# SparkySpecialKExpansion.net
KiCad netlist of a schematic drawn in EAGLE
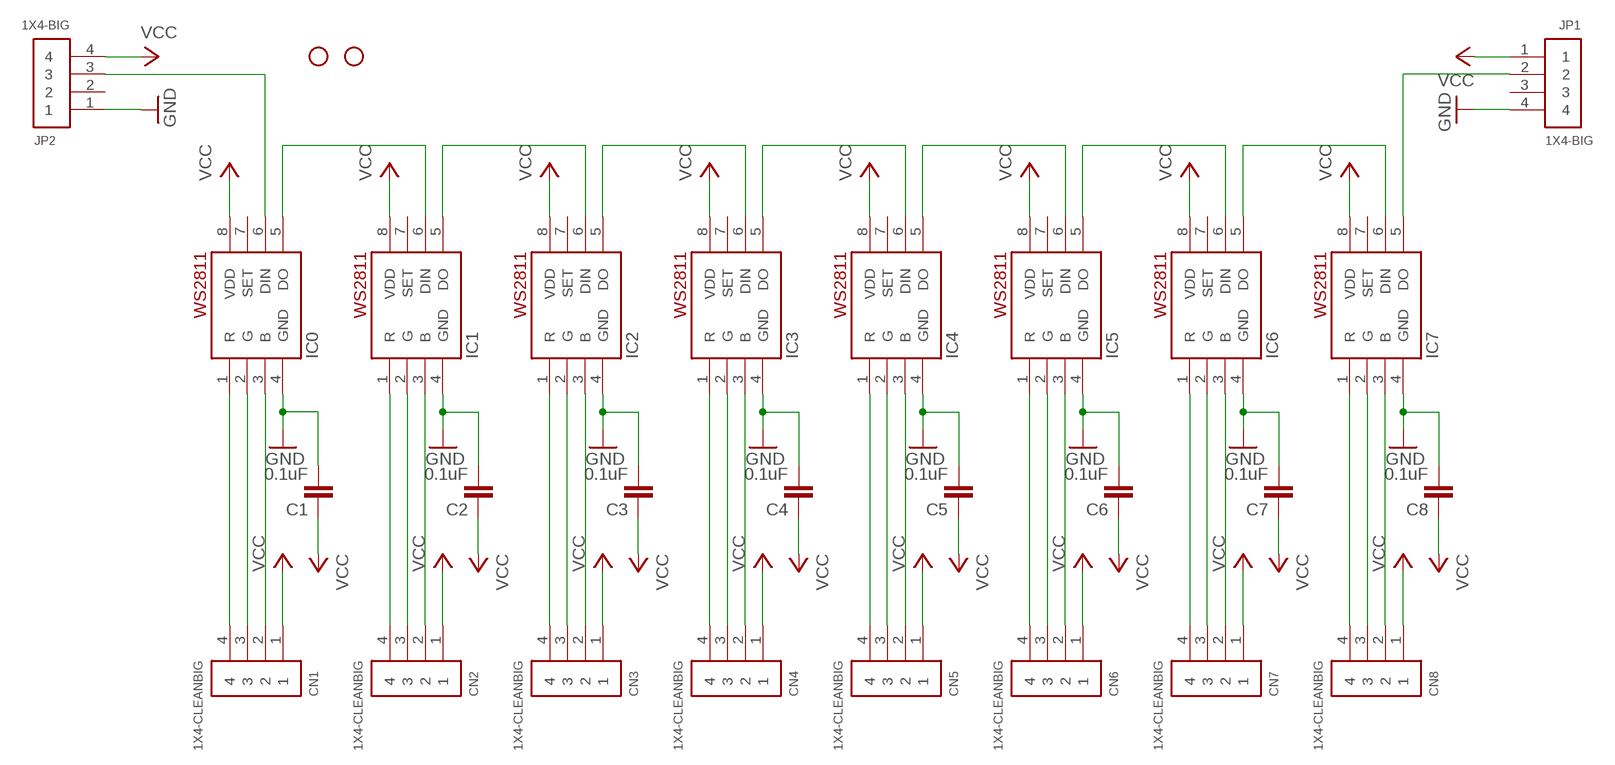
[diagram p0: schematic, sheet 1]

(export (version "E")
  (design (tool "Eeschema 10.0.6"))
  (components
    (comp (ref "C1")
      (value "0.1uF")
      (footprint "eagle-import:0805")
      (libsource (lib "eagle-import") (part "CAP0805"))
    )
    (comp (ref "C2")
      (value "0.1uF")
      (footprint "eagle-import:0805")
      (libsource (lib "eagle-import") (part "CAP0805"))
    )
    (comp (ref "C3")
      (value "0.1uF")
      (footprint "eagle-import:0805")
      (libsource (lib "eagle-import") (part "CAP0805"))
    )
    (comp (ref "C4")
      (value "0.1uF")
      (footprint "eagle-import:0805")
      (libsource (lib "eagle-import") (part "CAP0805"))
    )
    (comp (ref "C5")
      (value "0.1uF")
      (footprint "eagle-import:0805")
      (libsource (lib "eagle-import") (part "CAP0805"))
    )
    (comp (ref "C6")
      (value "0.1uF")
      (footprint "eagle-import:0805")
      (libsource (lib "eagle-import") (part "CAP0805"))
    )
    (comp (ref "C7")
      (value "0.1uF")
      (footprint "eagle-import:0805")
      (libsource (lib "eagle-import") (part "CAP0805"))
    )
    (comp (ref "C8")
      (value "0.1uF")
      (footprint "eagle-import:0805")
      (libsource (lib "eagle-import") (part "CAP0805"))
    )
    (comp (ref "CN1")
      (value "1X4-CLEANBIG")
      (footprint "eagle-import:1X04-CLEANBIG")
      (libsource (lib "eagle-import") (part "1X4-CLEANBIG"))
    )
    (comp (ref "CN2")
      (value "1X4-CLEANBIG")
      (footprint "eagle-import:1X04-CLEANBIG")
      (libsource (lib "eagle-import") (part "1X4-CLEANBIG"))
    )
    (comp (ref "CN3")
      (value "1X4-CLEANBIG")
      (footprint "eagle-import:1X04-CLEANBIG")
      (libsource (lib "eagle-import") (part "1X4-CLEANBIG"))
    )
    (comp (ref "CN4")
      (value "1X4-CLEANBIG")
      (footprint "eagle-import:1X04-CLEANBIG")
      (libsource (lib "eagle-import") (part "1X4-CLEANBIG"))
    )
    (comp (ref "CN5")
      (value "1X4-CLEANBIG")
      (footprint "eagle-import:1X04-CLEANBIG")
      (libsource (lib "eagle-import") (part "1X4-CLEANBIG"))
    )
    (comp (ref "CN6")
      (value "1X4-CLEANBIG")
      (footprint "eagle-import:1X04-CLEANBIG")
      (libsource (lib "eagle-import") (part "1X4-CLEANBIG"))
    )
    (comp (ref "CN7")
      (value "1X4-CLEANBIG")
      (footprint "eagle-import:1X04-CLEANBIG")
      (libsource (lib "eagle-import") (part "1X4-CLEANBIG"))
    )
    (comp (ref "CN8")
      (value "1X4-CLEANBIG")
      (footprint "eagle-import:1X04-CLEANBIG")
      (libsource (lib "eagle-import") (part "1X4-CLEANBIG"))
    )
    (comp (ref "IC0")
      (value "WS2811-SOP8")
      (footprint "eagle-import:SO08-SKINNYPADS")
      (libsource (lib "eagle-import") (part "WS2811-SOP8"))
    )
    (comp (ref "IC1")
      (value "WS2811-SOP8")
      (footprint "eagle-import:SO08-SKINNYPADS")
      (libsource (lib "eagle-import") (part "WS2811-SOP8"))
    )
    (comp (ref "IC2")
      (value "WS2811-SOP8")
      (footprint "eagle-import:SO08-SKINNYPADS")
      (libsource (lib "eagle-import") (part "WS2811-SOP8"))
    )
    (comp (ref "IC3")
      (value "WS2811-SOP8")
      (footprint "eagle-import:SO08-SKINNYPADS")
      (libsource (lib "eagle-import") (part "WS2811-SOP8"))
    )
    (comp (ref "IC4")
      (value "WS2811-SOP8")
      (footprint "eagle-import:SO08-SKINNYPADS")
      (libsource (lib "eagle-import") (part "WS2811-SOP8"))
    )
    (comp (ref "IC5")
      (value "WS2811-SOP8")
      (footprint "eagle-import:SO08-SKINNYPADS")
      (libsource (lib "eagle-import") (part "WS2811-SOP8"))
    )
    (comp (ref "IC6")
      (value "WS2811-SOP8")
      (footprint "eagle-import:SO08-SKINNYPADS")
      (libsource (lib "eagle-import") (part "WS2811-SOP8"))
    )
    (comp (ref "IC7")
      (value "WS2811-SOP8")
      (footprint "eagle-import:SO08-SKINNYPADS")
      (libsource (lib "eagle-import") (part "WS2811-SOP8"))
    )
    (comp (ref "JP1")
      (value "1X4-BIG")
      (footprint "eagle-import:1X04-BIG")
      (libsource (lib "eagle-import") (part "1X4-BIG"))
    )
    (comp (ref "JP2")
      (value "1X4-BIG")
      (footprint "eagle-import:1X04-BIG")
      (libsource (lib "eagle-import") (part "1X4-BIG"))
    )
    (comp (ref "JP3")
      (value "STAND-OFF")
      (footprint "eagle-import:STAND-OFF")
      (libsource (lib "eagle-import") (part "STAND-OFF"))
    )
    (comp (ref "JP4")
      (value "STAND-OFF")
      (footprint "eagle-import:STAND-OFF")
      (libsource (lib "eagle-import") (part "STAND-OFF"))
    )
  )
  (nets
    (net (code "1") (name "GND") (class "Default")
      (node (ref "C1") (pin "2") (pinfunction "2_2") (pintype "passive"))
      (node (ref "C2") (pin "2") (pinfunction "2_2") (pintype "passive"))
      (node (ref "C3") (pin "2") (pinfunction "2_2") (pintype "passive"))
      (node (ref "C4") (pin "2") (pinfunction "2_2") (pintype "passive"))
      (node (ref "C5") (pin "2") (pinfunction "2_2") (pintype "passive"))
      (node (ref "C6") (pin "2") (pinfunction "2_2") (pintype "passive"))
      (node (ref "C7") (pin "2") (pinfunction "2_2") (pintype "passive"))
      (node (ref "C8") (pin "2") (pinfunction "2_2") (pintype "passive"))
      (node (ref "IC0") (pin "4") (pinfunction "GND_4") (pintype "power_in"))
      (node (ref "IC1") (pin "4") (pinfunction "GND_4") (pintype "power_in"))
      (node (ref "IC2") (pin "4") (pinfunction "GND_4") (pintype "power_in"))
      (node (ref "IC3") (pin "4") (pinfunction "GND_4") (pintype "power_in"))
      (node (ref "IC4") (pin "4") (pinfunction "GND_4") (pintype "power_in"))
      (node (ref "IC5") (pin "4") (pinfunction "GND_4") (pintype "power_in"))
      (node (ref "IC6") (pin "4") (pinfunction "GND_4") (pintype "power_in"))
      (node (ref "IC7") (pin "4") (pinfunction "GND_4") (pintype "power_in"))
      (node (ref "JP1") (pin "4") (pinfunction "4_4") (pintype "bidirectional"))
      (node (ref "JP2") (pin "1") (pinfunction "1_1") (pintype "bidirectional"))
    )
    (net (code "2") (name "Net-(IC0-B)") (class "Default")
      (node (ref "CN1") (pin "2") (pinfunction "2_2") (pintype "bidirectional"))
      (node (ref "IC0") (pin "3") (pinfunction "B_3") (pintype "open_collector"))
    )
    (net (code "3") (name "Net-(IC0-DIN)") (class "Default")
      (node (ref "IC0") (pin "6") (pinfunction "DIN_6") (pintype "input"))
      (node (ref "JP2") (pin "3") (pinfunction "3_3") (pintype "bidirectional"))
    )
    (net (code "4") (name "Net-(IC0-DO)") (class "Default")
      (node (ref "IC0") (pin "5") (pinfunction "DO_5") (pintype "output"))
      (node (ref "IC1") (pin "6") (pinfunction "DIN_6") (pintype "input"))
    )
    (net (code "5") (name "Net-(IC0-G)") (class "Default")
      (node (ref "CN1") (pin "3") (pinfunction "3_3") (pintype "bidirectional"))
      (node (ref "IC0") (pin "2") (pinfunction "G_2") (pintype "open_collector"))
    )
    (net (code "6") (name "Net-(IC0-R)") (class "Default")
      (node (ref "CN1") (pin "4") (pinfunction "4_4") (pintype "bidirectional"))
      (node (ref "IC0") (pin "1") (pinfunction "R_1") (pintype "open_collector"))
    )
    (net (code "7") (name "Net-(IC1-B)") (class "Default")
      (node (ref "CN2") (pin "2") (pinfunction "2_2") (pintype "bidirectional"))
      (node (ref "IC1") (pin "3") (pinfunction "B_3") (pintype "open_collector"))
    )
    (net (code "8") (name "Net-(IC1-DO)") (class "Default")
      (node (ref "IC1") (pin "5") (pinfunction "DO_5") (pintype "output"))
      (node (ref "IC2") (pin "6") (pinfunction "DIN_6") (pintype "input"))
    )
    (net (code "9") (name "Net-(IC1-G)") (class "Default")
      (node (ref "CN2") (pin "3") (pinfunction "3_3") (pintype "bidirectional"))
      (node (ref "IC1") (pin "2") (pinfunction "G_2") (pintype "open_collector"))
    )
    (net (code "10") (name "Net-(IC1-R)") (class "Default")
      (node (ref "CN2") (pin "4") (pinfunction "4_4") (pintype "bidirectional"))
      (node (ref "IC1") (pin "1") (pinfunction "R_1") (pintype "open_collector"))
    )
    (net (code "11") (name "Net-(IC2-B)") (class "Default")
      (node (ref "CN3") (pin "2") (pinfunction "2_2") (pintype "bidirectional"))
      (node (ref "IC2") (pin "3") (pinfunction "B_3") (pintype "open_collector"))
    )
    (net (code "12") (name "Net-(IC2-DO)") (class "Default")
      (node (ref "IC2") (pin "5") (pinfunction "DO_5") (pintype "output"))
      (node (ref "IC3") (pin "6") (pinfunction "DIN_6") (pintype "input"))
    )
    (net (code "13") (name "Net-(IC2-G)") (class "Default")
      (node (ref "CN3") (pin "3") (pinfunction "3_3") (pintype "bidirectional"))
      (node (ref "IC2") (pin "2") (pinfunction "G_2") (pintype "open_collector"))
    )
    (net (code "14") (name "Net-(IC2-R)") (class "Default")
      (node (ref "CN3") (pin "4") (pinfunction "4_4") (pintype "bidirectional"))
      (node (ref "IC2") (pin "1") (pinfunction "R_1") (pintype "open_collector"))
    )
    (net (code "15") (name "Net-(IC3-B)") (class "Default")
      (node (ref "CN4") (pin "2") (pinfunction "2_2") (pintype "bidirectional"))
      (node (ref "IC3") (pin "3") (pinfunction "B_3") (pintype "open_collector"))
    )
    (net (code "16") (name "Net-(IC3-DO)") (class "Default")
      (node (ref "IC3") (pin "5") (pinfunction "DO_5") (pintype "output"))
      (node (ref "IC4") (pin "6") (pinfunction "DIN_6") (pintype "input"))
    )
    (net (code "17") (name "Net-(IC3-G)") (class "Default")
      (node (ref "CN4") (pin "3") (pinfunction "3_3") (pintype "bidirectional"))
      (node (ref "IC3") (pin "2") (pinfunction "G_2") (pintype "open_collector"))
    )
    (net (code "18") (name "Net-(IC3-R)") (class "Default")
      (node (ref "CN4") (pin "4") (pinfunction "4_4") (pintype "bidirectional"))
      (node (ref "IC3") (pin "1") (pinfunction "R_1") (pintype "open_collector"))
    )
    (net (code "19") (name "Net-(IC4-B)") (class "Default")
      (node (ref "CN5") (pin "2") (pinfunction "2_2") (pintype "bidirectional"))
      (node (ref "IC4") (pin "3") (pinfunction "B_3") (pintype "open_collector"))
    )
    (net (code "20") (name "Net-(IC4-DO)") (class "Default")
      (node (ref "IC4") (pin "5") (pinfunction "DO_5") (pintype "output"))
      (node (ref "IC5") (pin "6") (pinfunction "DIN_6") (pintype "input"))
    )
    (net (code "21") (name "Net-(IC4-G)") (class "Default")
      (node (ref "CN5") (pin "3") (pinfunction "3_3") (pintype "bidirectional"))
      (node (ref "IC4") (pin "2") (pinfunction "G_2") (pintype "open_collector"))
    )
    (net (code "22") (name "Net-(IC4-R)") (class "Default")
      (node (ref "CN5") (pin "4") (pinfunction "4_4") (pintype "bidirectional"))
      (node (ref "IC4") (pin "1") (pinfunction "R_1") (pintype "open_collector"))
    )
    (net (code "23") (name "Net-(IC5-B)") (class "Default")
      (node (ref "CN6") (pin "2") (pinfunction "2_2") (pintype "bidirectional"))
      (node (ref "IC5") (pin "3") (pinfunction "B_3") (pintype "open_collector"))
    )
    (net (code "24") (name "Net-(IC5-DO)") (class "Default")
      (node (ref "IC5") (pin "5") (pinfunction "DO_5") (pintype "output"))
      (node (ref "IC6") (pin "6") (pinfunction "DIN_6") (pintype "input"))
    )
    (net (code "25") (name "Net-(IC5-G)") (class "Default")
      (node (ref "CN6") (pin "3") (pinfunction "3_3") (pintype "bidirectional"))
      (node (ref "IC5") (pin "2") (pinfunction "G_2") (pintype "open_collector"))
    )
    (net (code "26") (name "Net-(IC5-R)") (class "Default")
      (node (ref "CN6") (pin "4") (pinfunction "4_4") (pintype "bidirectional"))
      (node (ref "IC5") (pin "1") (pinfunction "R_1") (pintype "open_collector"))
    )
    (net (code "27") (name "Net-(IC6-B)") (class "Default")
      (node (ref "CN7") (pin "2") (pinfunction "2_2") (pintype "bidirectional"))
      (node (ref "IC6") (pin "3") (pinfunction "B_3") (pintype "open_collector"))
    )
    (net (code "28") (name "Net-(IC6-DO)") (class "Default")
      (node (ref "IC6") (pin "5") (pinfunction "DO_5") (pintype "output"))
      (node (ref "IC7") (pin "6") (pinfunction "DIN_6") (pintype "input"))
    )
    (net (code "29") (name "Net-(IC6-G)") (class "Default")
      (node (ref "CN7") (pin "3") (pinfunction "3_3") (pintype "bidirectional"))
      (node (ref "IC6") (pin "2") (pinfunction "G_2") (pintype "open_collector"))
    )
    (net (code "30") (name "Net-(IC6-R)") (class "Default")
      (node (ref "CN7") (pin "4") (pinfunction "4_4") (pintype "bidirectional"))
      (node (ref "IC6") (pin "1") (pinfunction "R_1") (pintype "open_collector"))
    )
    (net (code "31") (name "Net-(IC7-B)") (class "Default")
      (node (ref "CN8") (pin "2") (pinfunction "2_2") (pintype "bidirectional"))
      (node (ref "IC7") (pin "3") (pinfunction "B_3") (pintype "open_collector"))
    )
    (net (code "32") (name "Net-(IC7-DO)") (class "Default")
      (node (ref "IC7") (pin "5") (pinfunction "DO_5") (pintype "output"))
      (node (ref "JP1") (pin "2") (pinfunction "2_2") (pintype "bidirectional"))
    )
    (net (code "33") (name "Net-(IC7-G)") (class "Default")
      (node (ref "CN8") (pin "3") (pinfunction "3_3") (pintype "bidirectional"))
      (node (ref "IC7") (pin "2") (pinfunction "G_2") (pintype "open_collector"))
    )
    (net (code "34") (name "Net-(IC7-R)") (class "Default")
      (node (ref "CN8") (pin "4") (pinfunction "4_4") (pintype "bidirectional"))
      (node (ref "IC7") (pin "1") (pinfunction "R_1") (pintype "open_collector"))
    )
    (net (code "35") (name "VCC") (class "Default")
      (node (ref "C1") (pin "1") (pinfunction "1_1") (pintype "passive"))
      (node (ref "C2") (pin "1") (pinfunction "1_1") (pintype "passive"))
      (node (ref "C3") (pin "1") (pinfunction "1_1") (pintype "passive"))
      (node (ref "C4") (pin "1") (pinfunction "1_1") (pintype "passive"))
      (node (ref "C5") (pin "1") (pinfunction "1_1") (pintype "passive"))
      (node (ref "C6") (pin "1") (pinfunction "1_1") (pintype "passive"))
      (node (ref "C7") (pin "1") (pinfunction "1_1") (pintype "passive"))
      (node (ref "C8") (pin "1") (pinfunction "1_1") (pintype "passive"))
      (node (ref "CN1") (pin "1") (pinfunction "1_1") (pintype "bidirectional"))
      (node (ref "CN2") (pin "1") (pinfunction "1_1") (pintype "bidirectional"))
      (node (ref "CN3") (pin "1") (pinfunction "1_1") (pintype "bidirectional"))
      (node (ref "CN4") (pin "1") (pinfunction "1_1") (pintype "bidirectional"))
      (node (ref "CN5") (pin "1") (pinfunction "1_1") (pintype "bidirectional"))
      (node (ref "CN6") (pin "1") (pinfunction "1_1") (pintype "bidirectional"))
      (node (ref "CN7") (pin "1") (pinfunction "1_1") (pintype "bidirectional"))
      (node (ref "CN8") (pin "1") (pinfunction "1_1") (pintype "bidirectional"))
      (node (ref "IC0") (pin "8") (pinfunction "VDD_8") (pintype "power_in"))
      (node (ref "IC1") (pin "8") (pinfunction "VDD_8") (pintype "power_in"))
      (node (ref "IC2") (pin "8") (pinfunction "VDD_8") (pintype "power_in"))
      (node (ref "IC3") (pin "8") (pinfunction "VDD_8") (pintype "power_in"))
      (node (ref "IC4") (pin "8") (pinfunction "VDD_8") (pintype "power_in"))
      (node (ref "IC5") (pin "8") (pinfunction "VDD_8") (pintype "power_in"))
      (node (ref "IC6") (pin "8") (pinfunction "VDD_8") (pintype "power_in"))
      (node (ref "IC7") (pin "8") (pinfunction "VDD_8") (pintype "power_in"))
      (node (ref "JP1") (pin "1") (pinfunction "1_1") (pintype "bidirectional"))
      (node (ref "JP2") (pin "4") (pinfunction "4_4") (pintype "bidirectional"))
    )
    (net (code "36") (name "unconnected-(IC0-SET-Pad7)") (class "Default")
      (node (ref "IC0") (pin "7") (pinfunction "SET_7") (pintype "input"))
    )
    (net (code "37") (name "unconnected-(IC1-SET-Pad7)") (class "Default")
      (node (ref "IC1") (pin "7") (pinfunction "SET_7") (pintype "input"))
    )
    (net (code "38") (name "unconnected-(IC2-SET-Pad7)") (class "Default")
      (node (ref "IC2") (pin "7") (pinfunction "SET_7") (pintype "input"))
    )
    (net (code "39") (name "unconnected-(IC3-SET-Pad7)") (class "Default")
      (node (ref "IC3") (pin "7") (pinfunction "SET_7") (pintype "input"))
    )
    (net (code "40") (name "unconnected-(IC4-SET-Pad7)") (class "Default")
      (node (ref "IC4") (pin "7") (pinfunction "SET_7") (pintype "input"))
    )
    (net (code "41") (name "unconnected-(IC5-SET-Pad7)") (class "Default")
      (node (ref "IC5") (pin "7") (pinfunction "SET_7") (pintype "input"))
    )
    (net (code "42") (name "unconnected-(IC6-SET-Pad7)") (class "Default")
      (node (ref "IC6") (pin "7") (pinfunction "SET_7") (pintype "input"))
    )
    (net (code "43") (name "unconnected-(IC7-SET-Pad7)") (class "Default")
      (node (ref "IC7") (pin "7") (pinfunction "SET_7") (pintype "input"))
    )
    (net (code "44") (name "unconnected-(JP1-Pad3)") (class "Default")
      (node (ref "JP1") (pin "3") (pinfunction "3_3") (pintype "bidirectional"))
    )
    (net (code "45") (name "unconnected-(JP2-Pad2)") (class "Default")
      (node (ref "JP2") (pin "2") (pinfunction "2_2") (pintype "bidirectional"))
    )
  )
)
